# BeatleBeat.net
KiCad netlist of a schematic drawn in EAGLE
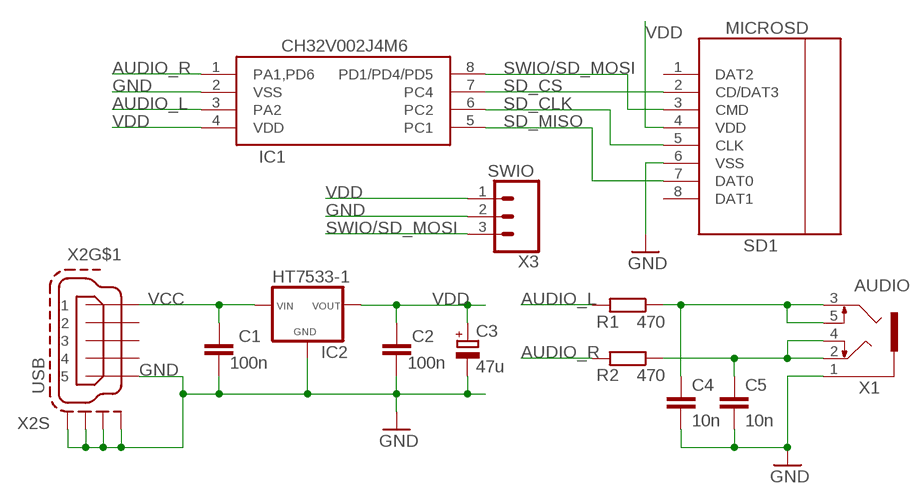
[diagram p0: schematic, sheet 1]

(export (version "E")
  (design (tool "Eeschema 10.0.6"))
  (components
    (comp (ref "C1")
      (value "100n")
      (footprint "eagle-import:C1206K")
      (libsource (lib "eagle-import") (part "C-EUC1206K"))
    )
    (comp (ref "C2")
      (value "100n")
      (footprint "eagle-import:C1206K")
      (libsource (lib "eagle-import") (part "C-EUC1206K"))
    )
    (comp (ref "C3")
      (value "47u")
      (footprint "eagle-import:C_6032-28R")
      (libsource (lib "eagle-import") (part "CPOL-EUC/6032-28R"))
    )
    (comp (ref "C4")
      (value "10n")
      (footprint "eagle-import:C1206K")
      (libsource (lib "eagle-import") (part "C-EUC1206K"))
    )
    (comp (ref "C5")
      (value "10n")
      (footprint "eagle-import:C1206K")
      (libsource (lib "eagle-import") (part "C-EUC1206K"))
    )
    (comp (ref "IC1")
      (value "CH32V002J4M6")
      (footprint "eagle-import:SOP8")
      (libsource (lib "eagle-import") (part "CH32V003J4M6"))
    )
    (comp (ref "IC2")
      (value "HT7533-1")
      (footprint "eagle-import:HT7533-1")
      (libsource (lib "eagle-import") (part "HT7533-1"))
    )
    (comp (ref "R1")
      (value "470")
      (footprint "eagle-import:M1206")
      (libsource (lib "eagle-import") (part "R-EU_M1206"))
    )
    (comp (ref "R2")
      (value "470")
      (footprint "eagle-import:M1206")
      (libsource (lib "eagle-import") (part "R-EU_M1206"))
    )
    (comp (ref "SD1")
      (value "MICROSD")
      (footprint "eagle-import:MICROSD")
      (libsource (lib "eagle-import") (part "MICROSD"))
    )
    (comp (ref "X1")
      (value "AUDIO")
      (footprint "eagle-import:1503_09")
      (libsource (lib "eagle-import") (part "1503_09"))
    )
    (comp (ref "X2")
      (value "USB")
      (footprint "eagle-import:32005-201")
      (libsource (lib "eagle-import") (part "MINI-USB-SCHIELD-32005-201"))
    )
    (comp (ref "X3")
      (value "SWIO")
      (footprint "eagle-import:1X03_LONGPADS")
      (libsource (lib "eagle-import") (part "CONN_03LONGPADS"))
    )
  )
  (nets
    (net (code "1") (name "/AUDIO_L") (class "Default")
      (node (ref "IC1") (pin "3") (pinfunction "PA2_3") (pintype "bidirectional"))
      (node (ref "R1") (pin "2") (pinfunction "2_2") (pintype "passive"))
    )
    (net (code "2") (name "/AUDIO_R") (class "Default")
      (node (ref "IC1") (pin "1") (pinfunction "PA1,PD6_1") (pintype "bidirectional"))
      (node (ref "R2") (pin "2") (pinfunction "2_2") (pintype "passive"))
    )
    (net (code "3") (name "/SD_CLK") (class "Default")
      (node (ref "IC1") (pin "6") (pinfunction "PC2_6") (pintype "bidirectional"))
      (node (ref "SD1") (pin "5") (pinfunction "CLK_5") (pintype "bidirectional"))
    )
    (net (code "4") (name "/SD_CS") (class "Default")
      (node (ref "IC1") (pin "7") (pinfunction "PC4_7") (pintype "bidirectional"))
      (node (ref "SD1") (pin "2") (pinfunction "CD/DAT3_2") (pintype "bidirectional"))
    )
    (net (code "5") (name "/SD_MISO") (class "Default")
      (node (ref "IC1") (pin "5") (pinfunction "PC1_5") (pintype "bidirectional"))
      (node (ref "SD1") (pin "7") (pinfunction "DAT0_7") (pintype "bidirectional"))
    )
    (net (code "6") (name "/SWIO{slash}SD_MOSI") (class "Default")
      (node (ref "IC1") (pin "8") (pinfunction "PD1/PD4/PD5_8") (pintype "bidirectional"))
      (node (ref "SD1") (pin "3") (pinfunction "CMD_3") (pintype "bidirectional"))
      (node (ref "X3") (pin "3") (pinfunction "3_3") (pintype "passive"))
    )
    (net (code "7") (name "/VCC") (class "Default")
      (node (ref "C1") (pin "1") (pinfunction "1_1") (pintype "passive"))
      (node (ref "IC2") (pin "VIN") (pinfunction "VIN_VIN") (pintype "input"))
      (node (ref "X2") (pin "1") (pinfunction "1_1") (pintype "passive"))
    )
    (net (code "8") (name "/VDD") (class "Default")
      (node (ref "C2") (pin "1") (pinfunction "1_1") (pintype "passive"))
      (node (ref "C3") (pin "+") (pinfunction "+_+") (pintype "passive"))
      (node (ref "IC1") (pin "4") (pinfunction "VDD_4") (pintype "power_in"))
      (node (ref "IC2") (pin "VOUT") (pinfunction "VOUT_VOUT") (pintype "passive"))
      (node (ref "SD1") (pin "4") (pinfunction "VDD_4") (pintype "bidirectional"))
      (node (ref "X3") (pin "1") (pinfunction "1_1") (pintype "passive"))
    )
    (net (code "9") (name "GND") (class "Default")
      (node (ref "C1") (pin "2") (pinfunction "2_2") (pintype "passive"))
      (node (ref "C2") (pin "2") (pinfunction "2_2") (pintype "passive"))
      (node (ref "C3") (pin "-") (pinfunction "-_-") (pintype "passive"))
      (node (ref "C4") (pin "2") (pinfunction "2_2") (pintype "passive"))
      (node (ref "C5") (pin "2") (pinfunction "2_2") (pintype "passive"))
      (node (ref "IC1") (pin "2") (pinfunction "VSS_2") (pintype "power_in"))
      (node (ref "IC2") (pin "GND") (pinfunction "GND_GND") (pintype "input"))
      (node (ref "SD1") (pin "6") (pinfunction "VSS_6") (pintype "bidirectional"))
      (node (ref "X1") (pin "1") (pinfunction "1_1") (pintype "passive"))
      (node (ref "X2") (pin "5") (pinfunction "5_5") (pintype "passive"))
      (node (ref "X2") (pin "M1") (pinfunction "S1_M1") (pintype "passive"))
      (node (ref "X2") (pin "M2") (pinfunction "S2_M2") (pintype "passive"))
      (node (ref "X2") (pin "M3") (pinfunction "S3_M3") (pintype "passive"))
      (node (ref "X2") (pin "M4") (pinfunction "S4_M4") (pintype "passive"))
      (node (ref "X3") (pin "2") (pinfunction "2_2") (pintype "passive"))
    )
    (net (code "10") (name "Net-(C4-Pad1)") (class "Default")
      (node (ref "C4") (pin "1") (pinfunction "1_1") (pintype "passive"))
      (node (ref "R1") (pin "1") (pinfunction "1_1") (pintype "passive"))
      (node (ref "X1") (pin "3") (pinfunction "3_3") (pintype "passive"))
      (node (ref "X1") (pin "5") (pinfunction "5_5") (pintype "passive"))
    )
    (net (code "11") (name "Net-(C5-Pad1)") (class "Default")
      (node (ref "C5") (pin "1") (pinfunction "1_1") (pintype "passive"))
      (node (ref "R2") (pin "1") (pinfunction "1_1") (pintype "passive"))
      (node (ref "X1") (pin "2") (pinfunction "2_2") (pintype "passive"))
      (node (ref "X1") (pin "4") (pinfunction "4_4") (pintype "passive"))
    )
    (net (code "12") (name "unconnected-(SD1-DAT1-Pad8)") (class "Default")
      (node (ref "SD1") (pin "8") (pinfunction "DAT1_8") (pintype "bidirectional"))
    )
    (net (code "13") (name "unconnected-(SD1-DAT2-Pad1)") (class "Default")
      (node (ref "SD1") (pin "1") (pinfunction "DAT2_1") (pintype "bidirectional"))
    )
    (net (code "14") (name "unconnected-(X2-Pad2)") (class "Default")
      (node (ref "X2") (pin "2") (pinfunction "2_2") (pintype "passive"))
    )
    (net (code "15") (name "unconnected-(X2-Pad3)") (class "Default")
      (node (ref "X2") (pin "3") (pinfunction "3_3") (pintype "passive"))
    )
    (net (code "16") (name "unconnected-(X2-Pad4)") (class "Default")
      (node (ref "X2") (pin "4") (pinfunction "4_4") (pintype "passive"))
    )
  )
)
